# Analog_Test.net
KiCad netlist of a schematic drawn in Altium Designer
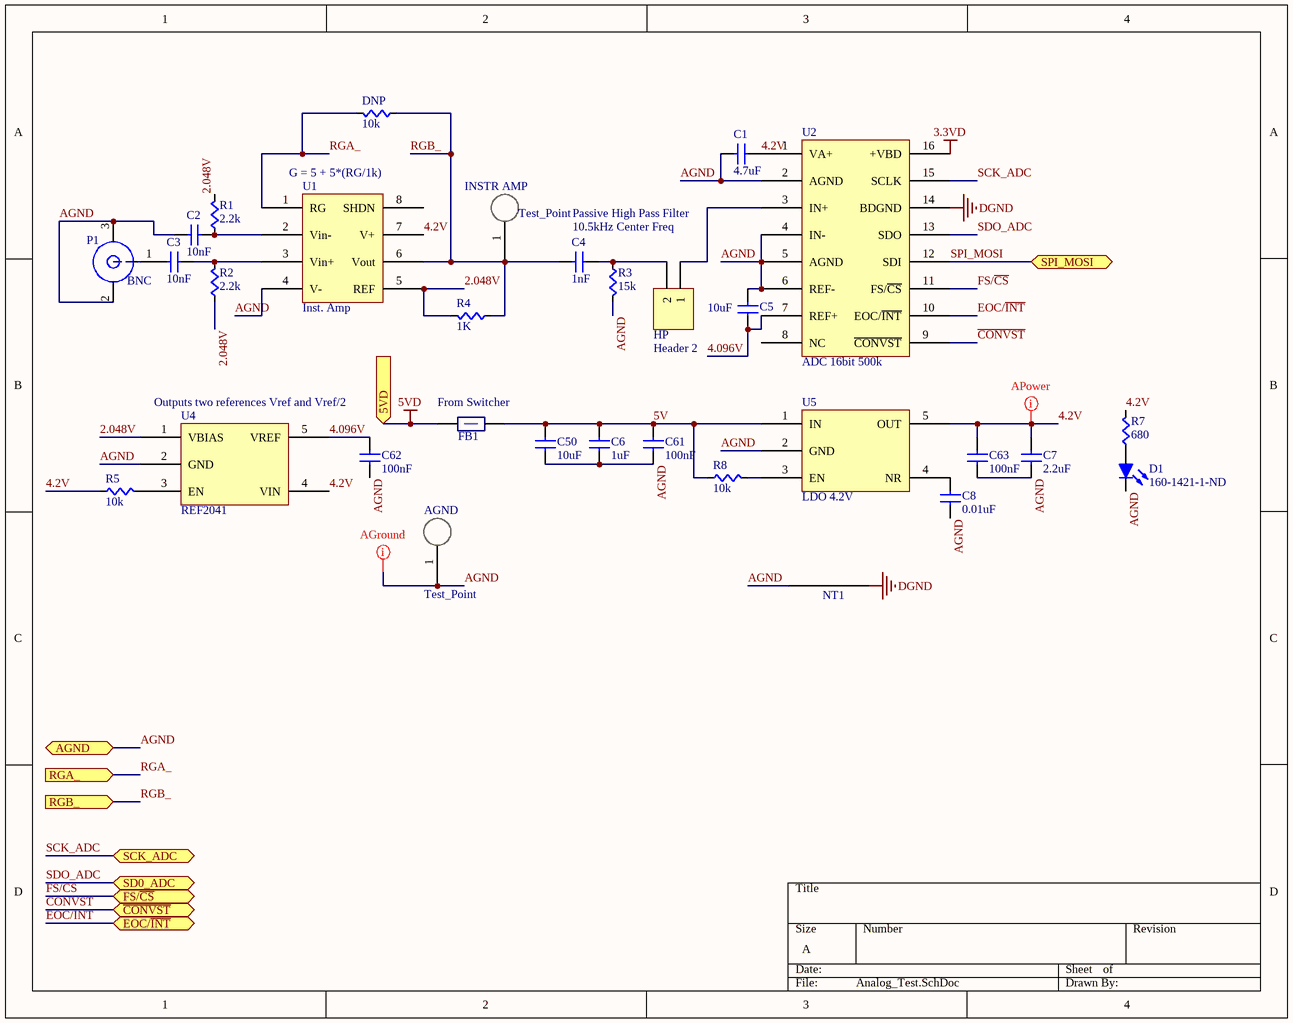
[diagram p0: Analog_Test.SchDoc]

(export (version "E")
  (design (tool "Eeschema 10.0.6"))
  (components
    (comp (ref "AGND")
      (value "Test_Point")
      (footprint "TP")
      (description "TEST POINT PC COMPACT .063\"D")
      (libsource (lib "Hydrophone") (part "Test_Point"))
    )
    (comp (ref "C1")
      (value "4.7uF")
      (footprint "CAPC0603")
      (fields (field (name "Comment") "Cap"))
      (libsource (lib "SubjuGator8") (part "Cap"))
    )
    (comp (ref "C2")
      (value "10nF")
      (footprint "CAPC0603")
      (fields (field (name "Comment") "Cap"))
      (libsource (lib "SubjuGator8") (part "Cap"))
    )
    (comp (ref "C3")
      (value "10nF")
      (footprint "CAPC0603")
      (fields (field (name "Comment") "Cap"))
      (libsource (lib "SubjuGator8") (part "Cap"))
    )
    (comp (ref "C4")
      (value "1nF")
      (footprint "CAPC0603")
      (fields (field (name "Comment") "Cap"))
      (libsource (lib "SubjuGator8") (part "Cap"))
    )
    (comp (ref "C5")
      (value "10uF")
      (footprint "CAPC0603")
      (fields (field (name "Comment") "Cap"))
      (libsource (lib "SubjuGator8") (part "Cap"))
    )
    (comp (ref "C6")
      (value "1uF")
      (footprint "CAPC0603")
      (fields (field (name "Comment") "Cap"))
      (libsource (lib "SubjuGator8") (part "Cap"))
    )
    (comp (ref "C7")
      (value "2.2uF")
      (footprint "CAPC0603")
      (fields (field (name "Comment") "Cap"))
      (libsource (lib "SubjuGator8") (part "Cap"))
    )
    (comp (ref "C8")
      (value "0.01uF")
      (footprint "CAPC0603")
      (fields (field (name "Comment") "Cap"))
      (libsource (lib "SubjuGator8") (part "Cap"))
    )
    (comp (ref "C50")
      (value "10uF")
      (footprint "CAPC0603")
      (fields (field (name "Comment") "Cap"))
      (libsource (lib "Passives") (part "Cap"))
    )
    (comp (ref "C61")
      (value "100nF")
      (footprint "CAPC0603")
      (fields (field (name "Comment") "Cap"))
      (libsource (lib "Passives") (part "Cap"))
    )
    (comp (ref "C62")
      (value "100nF")
      (footprint "CAPC0603")
      (fields (field (name "Comment") "Cap"))
      (libsource (lib "Passives") (part "Cap"))
    )
    (comp (ref "C63")
      (value "100nF")
      (footprint "CAPC0603")
      (fields (field (name "Comment") "Cap"))
      (libsource (lib "Passives") (part "Cap"))
    )
    (comp (ref "D1")
      (value "LED-RED")
      (footprint "Hydrophone:LED0805-RED")
      (description "Light Emitting Diode - RED")
      (fields
        (field (name "MANUFACTURER PART NUMBER") "LTST-C171CKT")
        (field (name "MANUFACTURER") "Lite-On Inc")
        (field (name "SUPPLIER PART NUMBER") "160-1421-1-ND")
      )
      (libsource (lib "Hydrophone") (part "LED-RED"))
    )
    (comp (ref "DNP")
      (value "10k")
      (footprint "RES0603")
      (fields (field (name "Comment") "Res"))
      (libsource (lib "SubjuGator8") (part "Res"))
    )
    (comp (ref "FB1")
      (value "FBead")
      (footprint "RES0603")
      (description "Ferrite Bead")
      (libsource (lib "Passives") (part "FBead"))
    )
    (comp (ref "HP")
      (value "Header 2")
      (footprint "HDR1X2")
      (description "Header, 2-Pin")
      (fields (field (name "PUBLISHER") "Altium Limited"))
      (libsource (lib "Miscellaneous Connectors") (part "Header 2"))
    )
    (comp (ref "INSTR AMP")
      (value "Test_Point")
      (footprint "TP")
      (description "TEST POINT PC COMPACT .063\"D")
      (libsource (lib "Hydrophone") (part "Test_Point"))
    )
    (comp (ref "NT1")
      (value "NetTie")
      (footprint "NT_5mil")
      (description "Ties two nets together")
      (libsource (lib "SubjuGator8") (part "NetTie"))
    )
    (comp (ref "P1")
      (value "BNC")
      (footprint "BNC Connector")
      (description "CONN BNC JACK R/A 50 OHM PCB")
      (libsource (lib "SubjuGator8") (part "BNC Connector"))
    )
    (comp (ref "R1")
      (value "2.2k")
      (footprint "RES0603")
      (fields (field (name "Comment") "Res"))
      (libsource (lib "SubjuGator8") (part "Res"))
    )
    (comp (ref "R2")
      (value "2.2k")
      (footprint "RES0603")
      (fields (field (name "Comment") "Res"))
      (libsource (lib "SubjuGator8") (part "Res"))
    )
    (comp (ref "R3")
      (value "15k")
      (footprint "RES0603")
      (fields (field (name "Comment") "Res"))
      (libsource (lib "SubjuGator8") (part "Res"))
    )
    (comp (ref "R4")
      (value "1K")
      (footprint "RES0603")
      (fields (field (name "Comment") "Res"))
      (libsource (lib "Passives") (part "Res"))
    )
    (comp (ref "R5")
      (value "10k")
      (footprint "RES0603")
      (fields (field (name "Comment") "Res"))
      (libsource (lib "SubjuGator8") (part "Res"))
    )
    (comp (ref "R7")
      (value "680")
      (footprint "RES0603")
      (fields (field (name "Comment") "Res"))
      (libsource (lib "SubjuGator8") (part "Res"))
    )
    (comp (ref "R8")
      (value "10k")
      (footprint "RES0603")
      (fields (field (name "Comment") "Res"))
      (libsource (lib "SubjuGator8") (part "Res"))
    )
    (comp (ref "U1")
      (value "Inst. Amp")
      (footprint "TSSOP-8n")
      (description "IC OPAMP INSTR 2MHZ RRO 8VSSOP")
      (libsource (lib "SubjuGator8") (part "INA331"))
    )
    (comp (ref "U2")
      (value "ADC 16bit 500k")
      (footprint "TSSOP-16pin")
      (description "IC ADC 16BIT 500KSPS 16-TSSOP")
      (libsource (lib "SubjuGator8") (part "ADC 16bit 500k"))
    )
    (comp (ref "U4")
      (value "REF2041")
      (footprint "SOT23-5")
      (description "IC VREF SERIES 2.05V/4.096V 5SOT")
      (libsource (lib "SubjuGator8") (part "REF2041"))
    )
    (comp (ref "U5")
      (value "LDO 4.2V")
      (footprint "sot23-5")
      (description "IC REG LDO 4.2V 0.2A 5SOT")
      (libsource (lib "SubjuGator8") (part "LDO 4.2V 200mA"))
    )
  )
  (nets
    (net (code "1") (name "/2.048V") (class "Default")
      (node (ref "R1") (pin "1") (pinfunction "A_1") (pintype "passive"))
      (node (ref "R2") (pin "2") (pinfunction "B_2") (pintype "passive"))
      (node (ref "R4") (pin "1") (pinfunction "A_1") (pintype "passive"))
      (node (ref "U1") (pin "5") (pinfunction "REF_5") (pintype "passive"))
      (node (ref "U4") (pin "1") (pinfunction "VBIAS_1") (pintype "passive"))
    )
    (net (code "2") (name "/4.2V") (class "Default")
      (node (ref "C1") (pin "2") (pinfunction "B_2") (pintype "passive"))
      (node (ref "C63") (pin "1") (pinfunction "A_1") (pintype "passive"))
      (node (ref "C7") (pin "2") (pinfunction "B_2") (pintype "passive"))
      (node (ref "R5") (pin "2") (pinfunction "B_2") (pintype "passive"))
      (node (ref "R7") (pin "1") (pinfunction "A_1") (pintype "passive"))
      (node (ref "U1") (pin "7") (pinfunction "V+_7") (pintype "passive"))
      (node (ref "U2") (pin "1") (pinfunction "VA+_1") (pintype "passive"))
      (node (ref "U4") (pin "4") (pinfunction "VIN_4") (pintype "passive"))
      (node (ref "U5") (pin "5") (pinfunction "OUT_5") (pintype "passive"))
    )
    (net (code "3") (name "/4.096V") (class "Default")
      (node (ref "C5") (pin "2") (pinfunction "B_2") (pintype "passive"))
      (node (ref "C62") (pin "1") (pinfunction "A_1") (pintype "passive"))
      (node (ref "U2") (pin "7") (pinfunction "REF+_7") (pintype "passive"))
      (node (ref "U4") (pin "5") (pinfunction "VREF_5") (pintype "passive"))
    )
    (net (code "4") (name "/5V") (class "Default")
      (node (ref "C50") (pin "1") (pinfunction "A_1") (pintype "passive"))
      (node (ref "C6") (pin "2") (pinfunction "B_2") (pintype "passive"))
      (node (ref "C61") (pin "1") (pinfunction "A_1") (pintype "passive"))
      (node (ref "FB1") (pin "2") (pinfunction "B_2") (pintype "passive"))
      (node (ref "R8") (pin "2") (pinfunction "B_2") (pintype "passive"))
      (node (ref "U5") (pin "1") (pinfunction "IN_1") (pintype "passive"))
    )
    (net (code "5") (name "/AGND") (class "Default")
      (node (ref "AGND") (pin "1") (pintype "passive"))
      (node (ref "C1") (pin "1") (pinfunction "A_1") (pintype "passive"))
      (node (ref "C2") (pin "1") (pinfunction "A_1") (pintype "passive"))
      (node (ref "C5") (pin "1") (pinfunction "A_1") (pintype "passive"))
      (node (ref "C50") (pin "2") (pinfunction "B_2") (pintype "passive"))
      (node (ref "C6") (pin "1") (pinfunction "A_1") (pintype "passive"))
      (node (ref "C61") (pin "2") (pinfunction "B_2") (pintype "passive"))
      (node (ref "C62") (pin "2") (pinfunction "B_2") (pintype "passive"))
      (node (ref "C63") (pin "2") (pinfunction "B_2") (pintype "passive"))
      (node (ref "C7") (pin "1") (pinfunction "A_1") (pintype "passive"))
      (node (ref "C8") (pin "1") (pinfunction "A_1") (pintype "passive"))
      (node (ref "D1") (pin "1") (pinfunction "K_1") (pintype "passive"))
      (node (ref "NT1") (pin "1") (pinfunction "1_1") (pintype "passive"))
      (node (ref "P1") (pin "2") (pinfunction "GND_2") (pintype "passive"))
      (node (ref "P1") (pin "3") (pinfunction "GND_3") (pintype "passive"))
      (node (ref "R3") (pin "1") (pinfunction "A_1") (pintype "passive"))
      (node (ref "U1") (pin "4") (pinfunction "V-_4") (pintype "passive"))
      (node (ref "U2") (pin "2") (pinfunction "AGND_2") (pintype "passive"))
      (node (ref "U2") (pin "4") (pinfunction "IN-_4") (pintype "passive"))
      (node (ref "U2") (pin "5") (pinfunction "AGND_5") (pintype "passive"))
      (node (ref "U2") (pin "6") (pinfunction "REF-_6") (pintype "passive"))
      (node (ref "U4") (pin "2") (pinfunction "GND_2") (pintype "passive"))
      (node (ref "U5") (pin "2") (pinfunction "GND_2") (pintype "passive"))
    )
    (net (code "6") (name "/EOC{slash}~{INT}") (class "Default")
      (node (ref "U2") (pin "10") (pinfunction "EOC/~{INT}_10") (pintype "passive"))
    )
    (net (code "7") (name "/FS{slash}~{CS}") (class "Default")
      (node (ref "U2") (pin "11") (pinfunction "FS/~{CS}_11") (pintype "passive"))
    )
    (net (code "8") (name "/RGA_") (class "Default")
      (node (ref "DNP") (pin "1") (pinfunction "A_1") (pintype "passive"))
      (node (ref "U1") (pin "1") (pinfunction "RG_1") (pintype "passive"))
    )
    (net (code "9") (name "/RGB_") (class "Default")
      (node (ref "C4") (pin "1") (pinfunction "A_1") (pintype "passive"))
      (node (ref "DNP") (pin "2") (pinfunction "B_2") (pintype "passive"))
      (node (ref "INSTR AMP") (pin "1") (pintype "passive"))
      (node (ref "R4") (pin "2") (pinfunction "B_2") (pintype "passive"))
      (node (ref "U1") (pin "6") (pinfunction "Vout_6") (pintype "passive"))
    )
    (net (code "10") (name "/SCK_ADC") (class "Default")
      (node (ref "U2") (pin "15") (pinfunction "SCLK_15") (pintype "passive"))
    )
    (net (code "11") (name "/SDO_ADC") (class "Default")
      (node (ref "U2") (pin "13") (pinfunction "SDO_13") (pintype "passive"))
    )
    (net (code "12") (name "/SPI_MOSI") (class "Default")
      (node (ref "U2") (pin "12") (pinfunction "SDI_12") (pintype "passive"))
    )
    (net (code "13") (name "/~{CONVST}") (class "Default")
      (node (ref "U2") (pin "9") (pinfunction "~{CONVST}_9") (pintype "passive"))
    )
    (net (code "14") (name "3.3VD") (class "Default")
      (node (ref "U2") (pin "16") (pinfunction "+VBD_16") (pintype "passive"))
    )
    (net (code "15") (name "5VD") (class "Default")
      (node (ref "FB1") (pin "1") (pinfunction "A_1") (pintype "passive"))
    )
    (net (code "16") (name "DGND") (class "Default")
      (node (ref "NT1") (pin "2") (pinfunction "2_2") (pintype "passive"))
      (node (ref "U2") (pin "14") (pinfunction "BDGND_14") (pintype "passive"))
    )
    (net (code "17") (name "Net-(C2-B)") (class "Default")
      (node (ref "C2") (pin "2") (pinfunction "B_2") (pintype "passive"))
      (node (ref "R1") (pin "2") (pinfunction "B_2") (pintype "passive"))
      (node (ref "U1") (pin "2") (pinfunction "Vin-_2") (pintype "passive"))
    )
    (net (code "18") (name "Net-(C3-A)") (class "Default")
      (node (ref "C3") (pin "1") (pinfunction "A_1") (pintype "passive"))
      (node (ref "P1") (pin "1") (pinfunction "Signal_1") (pintype "passive"))
    )
    (net (code "19") (name "Net-(C3-B)") (class "Default")
      (node (ref "C3") (pin "2") (pinfunction "B_2") (pintype "passive"))
      (node (ref "R2") (pin "1") (pinfunction "A_1") (pintype "passive"))
      (node (ref "U1") (pin "3") (pinfunction "Vin+_3") (pintype "passive"))
    )
    (net (code "20") (name "Net-(C4-B)") (class "Default")
      (node (ref "C4") (pin "2") (pinfunction "B_2") (pintype "passive"))
      (node (ref "HP") (pin "2") (pinfunction "2_2") (pintype "passive"))
      (node (ref "R3") (pin "2") (pinfunction "B_2") (pintype "passive"))
    )
    (net (code "21") (name "Net-(C8-B)") (class "Default")
      (node (ref "C8") (pin "2") (pinfunction "B_2") (pintype "passive"))
      (node (ref "U5") (pin "4") (pinfunction "NR_4") (pintype "passive"))
    )
    (net (code "22") (name "Net-(D1-A)") (class "Default")
      (node (ref "D1") (pin "2") (pinfunction "A_2") (pintype "passive"))
      (node (ref "R7") (pin "2") (pinfunction "B_2") (pintype "passive"))
    )
    (net (code "23") (name "Net-(R5-A)") (class "Default")
      (node (ref "R5") (pin "1") (pinfunction "A_1") (pintype "passive"))
      (node (ref "U4") (pin "3") (pinfunction "EN_3") (pintype "passive"))
    )
    (net (code "24") (name "Net-(R8-A)") (class "Default")
      (node (ref "R8") (pin "1") (pinfunction "A_1") (pintype "passive"))
      (node (ref "U5") (pin "3") (pinfunction "EN_3") (pintype "passive"))
    )
    (net (code "25") (name "Net-(U2-IN+)") (class "Default")
      (node (ref "HP") (pin "1") (pinfunction "1_1") (pintype "passive"))
      (node (ref "U2") (pin "3") (pinfunction "IN+_3") (pintype "passive"))
    )
    (net (code "26") (name "unconnected-(U1-SHDN-Pad8)") (class "Default")
      (node (ref "U1") (pin "8") (pinfunction "SHDN_8") (pintype "passive"))
    )
    (net (code "27") (name "unconnected-(U2-NC-Pad8)") (class "Default")
      (node (ref "U2") (pin "8") (pinfunction "NC_8") (pintype "passive"))
    )
  )
)
